# Reference-L.net
KiCad netlist of a schematic drawn in Altium Designer
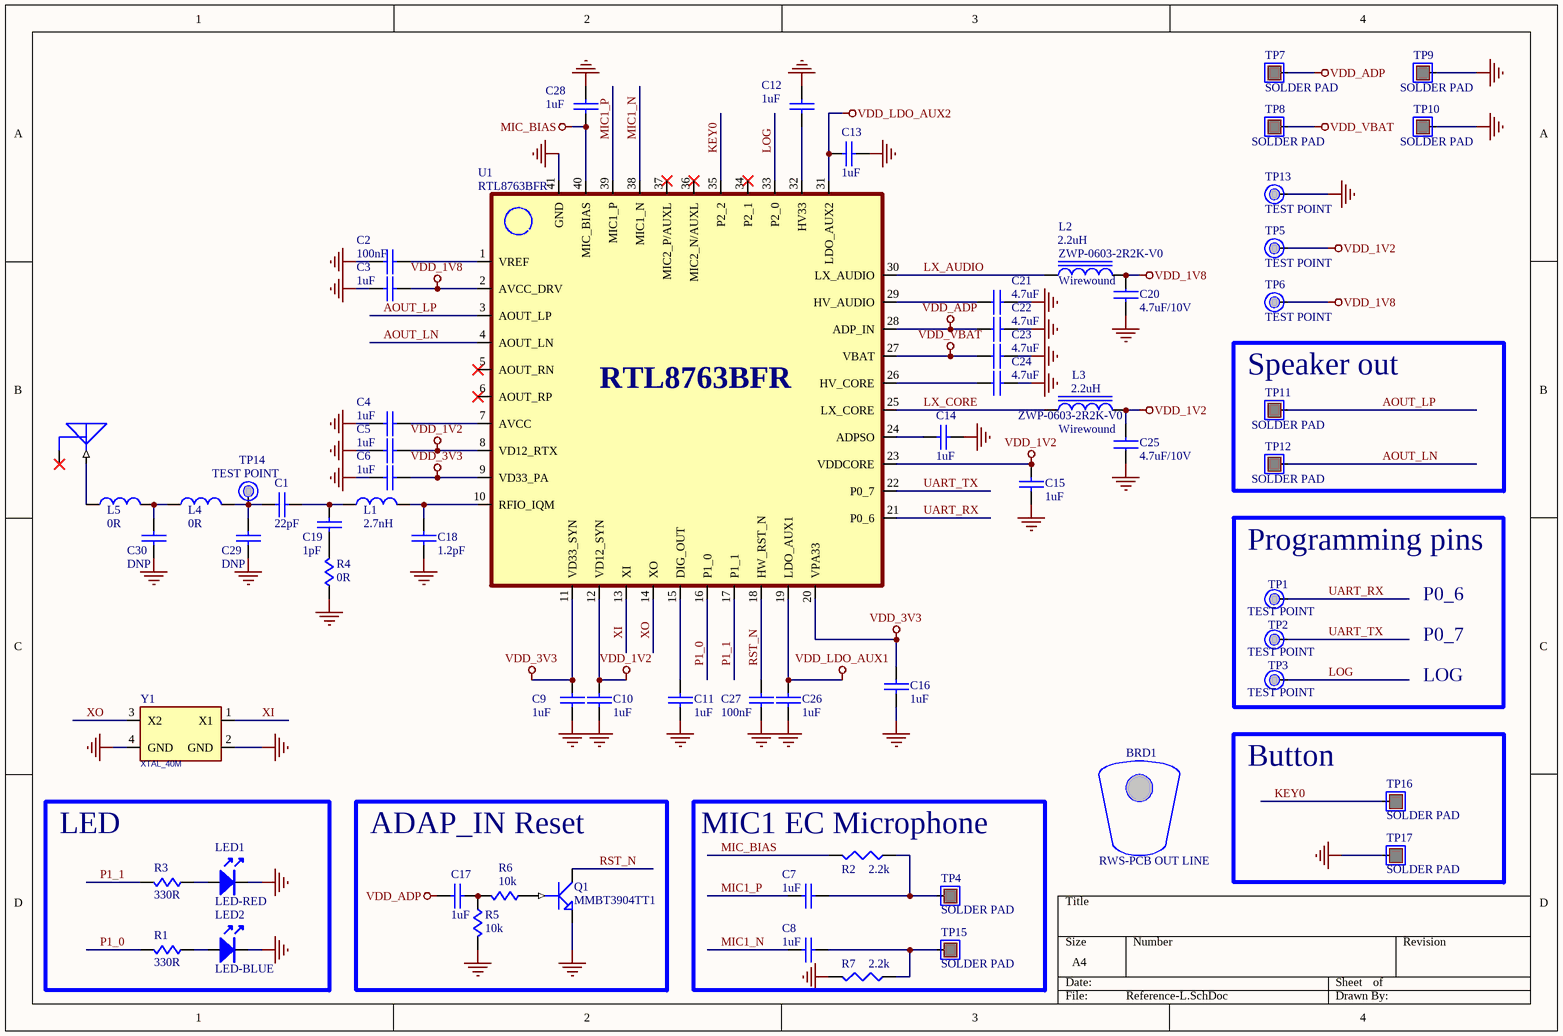
[diagram p0: Reference-L.SchDoc]

(export (version "E")
  (design (tool "Eeschema 10.0.6"))
  (components
    (comp (ref "ANT1")
      (value "ANTENNA-2")
      (footprint "ANT-ACX-AT8010")
      (libsource (lib "*") (part "ANTENNA-2_4"))
    )
    (comp (ref "BRD1")
      (value "RWS-PCB OUT LINE")
      (footprint "BOARD-L")
      (libsource (lib "*") (part "RWS-PCB OUT LINE"))
    )
    (comp (ref "C1")
      (value "22pF")
      (footprint "CAP_0201")
      (description "Capacitor")
      (libsource (lib "*") (part "CAP"))
    )
    (comp (ref "C2")
      (value "100nF")
      (footprint "CAP_0201")
      (description "Capacitor")
      (libsource (lib "*") (part "CAP"))
    )
    (comp (ref "C3")
      (value "1uF")
      (footprint "CAP_0201")
      (description "Capacitor")
      (libsource (lib "*") (part "CAP"))
    )
    (comp (ref "C4")
      (value "1uF")
      (footprint "CAP_0201")
      (description "Capacitor")
      (libsource (lib "*") (part "CAP"))
    )
    (comp (ref "C5")
      (value "1uF")
      (footprint "CAP_0201")
      (description "Capacitor")
      (libsource (lib "*") (part "CAP"))
    )
    (comp (ref "C6")
      (value "1uF")
      (footprint "CAP_0201")
      (description "Capacitor")
      (libsource (lib "*") (part "CAP"))
    )
    (comp (ref "C7")
      (value "1uF")
      (footprint "CAP_0201")
      (description "Capacitor")
      (libsource (lib "*") (part "CAP"))
    )
    (comp (ref "C8")
      (value "1uF")
      (footprint "CAP_0201")
      (description "Capacitor")
      (libsource (lib "*") (part "CAP"))
    )
    (comp (ref "C9")
      (value "1uF")
      (footprint "CAP_0201")
      (description "Capacitor")
      (libsource (lib "*") (part "CAP"))
    )
    (comp (ref "C10")
      (value "1uF")
      (footprint "CAP_0201")
      (description "Capacitor")
      (libsource (lib "*") (part "CAP"))
    )
    (comp (ref "C11")
      (value "1uF")
      (footprint "CAP_0201")
      (description "Capacitor")
      (libsource (lib "*") (part "CAP"))
    )
    (comp (ref "C12")
      (value "1uF")
      (footprint "CAP_0201")
      (description "Capacitor")
      (libsource (lib "*") (part "CAP"))
    )
    (comp (ref "C13")
      (value "1uF")
      (footprint "CAP_0201")
      (description "Capacitor")
      (libsource (lib "*") (part "CAP"))
    )
    (comp (ref "C14")
      (value "1uF")
      (footprint "CAP_0201")
      (description "Capacitor")
      (libsource (lib "*") (part "CAP"))
    )
    (comp (ref "C15")
      (value "1uF")
      (footprint "CAP_0201")
      (description "Capacitor")
      (libsource (lib "*") (part "CAP"))
    )
    (comp (ref "C16")
      (value "1uF")
      (footprint "CAP_0201")
      (description "Capacitor")
      (libsource (lib "*") (part "CAP"))
    )
    (comp (ref "C17")
      (value "1uF")
      (footprint "CAP_0201")
      (description "Capacitor")
      (libsource (lib "*") (part "CAP"))
    )
    (comp (ref "C18")
      (value "1.2pF")
      (footprint "CAP_0201")
      (description "Capacitor")
      (libsource (lib "*") (part "CAP"))
    )
    (comp (ref "C19")
      (value "1pF")
      (footprint "CAP_0201")
      (description "Capacitor")
      (libsource (lib "*") (part "CAP"))
    )
    (comp (ref "C20")
      (value "4.7uF/10V")
      (footprint "CAP_0402")
      (description "CHIP CAP 4.7uF 6.3V K 0603  X5R")
      (fields (field (name "PART NUMBER") "CC0603ZRY5V5BB475") (field (name "TOLERANCE") "+80-20％"))
      (libsource (lib "*") (part "4.7uF"))
    )
    (comp (ref "C21")
      (value "4.7uF")
      (footprint "CAP_0402")
      (description "CHIP CAP 4.7uF 6.3V K 0603  X5R")
      (fields (field (name "PART NUMBER") "CC0603ZRY5V5BB475") (field (name "TOLERANCE") "+80-20％"))
      (libsource (lib "*") (part "4.7uF"))
    )
    (comp (ref "C22")
      (value "4.7uF")
      (footprint "CAP_0402")
      (description "CHIP CAP 4.7uF 6.3V K 0603  X5R")
      (fields (field (name "PART NUMBER") "CC0603ZRY5V5BB475") (field (name "TOLERANCE") "+80-20％"))
      (libsource (lib "*") (part "4.7uF"))
    )
    (comp (ref "C23")
      (value "4.7uF")
      (footprint "CAP_0402")
      (description "CHIP CAP 4.7uF 6.3V K 0603  X5R")
      (fields (field (name "PART NUMBER") "CC0603ZRY5V5BB475") (field (name "TOLERANCE") "+80-20％"))
      (libsource (lib "*") (part "4.7uF"))
    )
    (comp (ref "C24")
      (value "4.7uF")
      (footprint "CAP_0402")
      (description "CHIP CAP 4.7uF 6.3V K 0603  X5R")
      (fields (field (name "PART NUMBER") "CC0603ZRY5V5BB475") (field (name "TOLERANCE") "+80-20％"))
      (libsource (lib "*") (part "4.7uF"))
    )
    (comp (ref "C25")
      (value "4.7uF/10V")
      (footprint "CAP_0402")
      (description "CHIP CAP 4.7uF 6.3V K 0603  X5R")
      (fields (field (name "PART NUMBER") "CC0603ZRY5V5BB475") (field (name "TOLERANCE") "+80-20％"))
      (libsource (lib "*") (part "4.7uF"))
    )
    (comp (ref "C26")
      (value "1uF")
      (footprint "CAP_0201")
      (description "Capacitor")
      (libsource (lib "*") (part "CAP"))
    )
    (comp (ref "C27")
      (value "100nF")
      (footprint "CAP_0201")
      (description "Capacitor")
      (libsource (lib "*") (part "CAP"))
    )
    (comp (ref "C28")
      (value "1uF")
      (footprint "CAP_0201")
      (description "Capacitor")
      (libsource (lib "*") (part "CAP"))
    )
    (comp (ref "C29")
      (value "DNP")
      (footprint "CAP_0201")
      (description "Capacitor")
      (libsource (lib "*") (part "CAP"))
    )
    (comp (ref "C30")
      (value "DNP")
      (footprint "CAP_0201")
      (description "Capacitor")
      (libsource (lib "*") (part "CAP"))
    )
    (comp (ref "L1") (value "2.7nH") (footprint "IND_0201") (libsource (lib "*") (part "INDUCTOR-MINI")))
    (comp (ref "L2") (value "2.2uH") (footprint "IND_0603") (libsource (lib "*") (part "INDUCTOR IRON")))
    (comp (ref "L3") (value "2.2uH") (footprint "IND_0603") (libsource (lib "*") (part "INDUCTOR IRON")))
    (comp (ref "L4") (value "0R") (footprint "IND_0201") (libsource (lib "*") (part "INDUCTOR-MINI")))
    (comp (ref "L5") (value "0R") (footprint "IND_0201") (libsource (lib "*") (part "INDUCTOR-MINI")))
    (comp (ref "LED1") (value "LED-RED") (footprint "LED-0603") (libsource (lib "*") (part "LED")))
    (comp (ref "LED2") (value "LED-BLUE") (footprint "LED-0603") (libsource (lib "*") (part "LED")))
    (comp (ref "Q1") (value "MMBT3904TT1") (footprint "SOT323") (libsource (lib "*") (part "NPN")))
    (comp (ref "R1") (value "330R") (footprint "RES_0201") (libsource (lib "*") (part "RESISTANCE")))
    (comp (ref "R2")
      (value "2.2k")
      (footprint "0201")
      (description "CHIP RES 1.5K 1/16W 0402")
      (fields (field (name "TOLERANCE") "±5％") (field (name "PART NUMBER") "RC0402FR-071K5L"))
      (libsource (lib "*") (part "1.5K"))
    )
    (comp (ref "R3") (value "330R") (footprint "RES_0201") (libsource (lib "*") (part "RESISTANCE")))
    (comp (ref "R4") (value "0R") (footprint "RES_0201") (libsource (lib "*") (part "RESISTANCE")))
    (comp (ref "R5") (value "10k") (footprint "RES_0201") (libsource (lib "*") (part "RESISTANCE")))
    (comp (ref "R6") (value "10k") (footprint "RES_0201") (libsource (lib "*") (part "RESISTANCE")))
    (comp (ref "R7")
      (value "2.2k")
      (footprint "0201")
      (description "CHIP RES 1.5K 1/16W 0402")
      (fields (field (name "TOLERANCE") "±5％") (field (name "PART NUMBER") "RC0402FR-071K5L"))
      (libsource (lib "*") (part "1.5K"))
    )
    (comp (ref "TP1") (value "TEST POINT") (footprint "TP-0.8MM") (libsource (lib "*") (part "TEST POINT")))
    (comp (ref "TP2") (value "TEST POINT") (footprint "TP-0.8MM") (libsource (lib "*") (part "TEST POINT")))
    (comp (ref "TP3") (value "TEST POINT") (footprint "TP-0.8MM") (libsource (lib "*") (part "TEST POINT")))
    (comp (ref "TP4")
      (value "SOLDER PAD")
      (footprint "TP-SOLDER")
      (libsource (lib "") (part "TEST POINT-SQ_1"))
    )
    (comp (ref "TP5") (value "TEST POINT") (footprint "TP-0.8MM") (libsource (lib "*") (part "TEST POINT")))
    (comp (ref "TP6") (value "TEST POINT") (footprint "TP-0.8MM") (libsource (lib "*") (part "TEST POINT")))
    (comp (ref "TP7")
      (value "SOLDER PAD")
      (footprint "TP-SOLDER-SQ")
      (libsource (lib "*") (part "TEST POINT-SQ"))
    )
    (comp (ref "TP8")
      (value "SOLDER PAD")
      (footprint "TP-SOLDER-SQ")
      (libsource (lib "*") (part "TEST POINT-SQ"))
    )
    (comp (ref "TP9")
      (value "SOLDER PAD")
      (footprint "TP-SOLDER")
      (libsource (lib "*") (part "TEST POINT-SQ"))
    )
    (comp (ref "TP10")
      (value "SOLDER PAD")
      (footprint "TP-SOLDER")
      (libsource (lib "*") (part "TEST POINT-SQ"))
    )
    (comp (ref "TP11")
      (value "SOLDER PAD")
      (footprint "TP-SOLDER")
      (libsource (lib "*") (part "TEST POINT-SQ"))
    )
    (comp (ref "TP12")
      (value "SOLDER PAD")
      (footprint "TP-SOLDER")
      (libsource (lib "*") (part "TEST POINT-SQ"))
    )
    (comp (ref "TP13") (value "TEST POINT") (footprint "TP-0.8MM") (libsource (lib "*") (part "TEST POINT")))
    (comp (ref "TP14") (value "TEST POINT") (footprint "TP-0.8MM") (libsource (lib "*") (part "TEST POINT")))
    (comp (ref "TP15")
      (value "SOLDER PAD")
      (footprint "TP-SOLDER")
      (libsource (lib "") (part "TEST POINT-SQ_1"))
    )
    (comp (ref "TP16")
      (value "SOLDER PAD")
      (footprint "TP-SOLDER-SQ")
      (libsource (lib "") (part "TEST POINT-SQ_1"))
    )
    (comp (ref "TP17")
      (value "SOLDER PAD")
      (footprint "TP-SOLDER-SQ")
      (libsource (lib "") (part "TEST POINT-SQ_1"))
    )
    (comp (ref "U1")
      (value "RTL8763BFR")
      (footprint "QFN40-0.4-5X5")
      (description "RTL8763")
      (libsource (lib "*") (part "RTL8763"))
    )
    (comp (ref "Y1")
      (value "XTAL_40M")
      (footprint "CRY_2.5X2.0")
      (description "S2520A-040000-T12-BBK-1AHA(YOKE)")
      (fields (field (name "PART NUMBER") "40M xtal 2.5x2.0"))
      (libsource (lib "*") (part "XTAL"))
    )
  )
  (nets
    (net (code "1") (name "/AOUT_LN") (class "Default")
      (node (ref "TP12") (pin "1") (pinfunction "1_1") (pintype "passive"))
      (node (ref "U1") (pin "4") (pinfunction "AOUT_LN_4") (pintype "passive"))
    )
    (net (code "2") (name "/AOUT_LP") (class "Default")
      (node (ref "TP11") (pin "1") (pinfunction "1_1") (pintype "passive"))
      (node (ref "U1") (pin "3") (pinfunction "AOUT_LP_3") (pintype "passive"))
    )
    (net (code "3") (name "/KEY0") (class "Default")
      (node (ref "TP16") (pin "1") (pinfunction "1_1") (pintype "passive"))
      (node (ref "U1") (pin "35") (pinfunction "P2_2_35") (pintype "passive"))
    )
    (net (code "4") (name "/LOG") (class "Default")
      (node (ref "TP3") (pin "1") (pinfunction "1_1") (pintype "passive"))
      (node (ref "U1") (pin "33") (pinfunction "P2_0_33") (pintype "passive"))
    )
    (net (code "5") (name "/LX_AUDIO") (class "Default")
      (node (ref "L2") (pin "1") (pinfunction "1_1") (pintype "passive"))
      (node (ref "U1") (pin "30") (pinfunction "LX_AUDIO_30") (pintype "passive"))
    )
    (net (code "6") (name "/LX_CORE") (class "Default")
      (node (ref "L3") (pin "1") (pinfunction "1_1") (pintype "passive"))
      (node (ref "U1") (pin "25") (pinfunction "LX_CORE_25") (pintype "passive"))
    )
    (net (code "7") (name "/MIC1_N") (class "Default")
      (node (ref "C8") (pin "1") (pinfunction "1_1") (pintype "passive"))
      (node (ref "U1") (pin "38") (pinfunction "MIC1_N_38") (pintype "passive"))
    )
    (net (code "8") (name "/MIC1_P") (class "Default")
      (node (ref "C7") (pin "1") (pinfunction "1_1") (pintype "passive"))
      (node (ref "U1") (pin "39") (pinfunction "MIC1_P_39") (pintype "passive"))
    )
    (net (code "9") (name "/P1_0") (class "Default")
      (node (ref "R1") (pin "2") (pinfunction "2_2") (pintype "passive"))
      (node (ref "U1") (pin "16") (pinfunction "P1_0_16") (pintype "passive"))
    )
    (net (code "10") (name "/P1_1") (class "Default")
      (node (ref "R3") (pin "2") (pinfunction "2_2") (pintype "passive"))
      (node (ref "U1") (pin "17") (pinfunction "P1_1_17") (pintype "passive"))
    )
    (net (code "11") (name "/RST_N") (class "Default")
      (node (ref "C27") (pin "1") (pinfunction "1_1") (pintype "passive"))
      (node (ref "Q1") (pin "3") (pinfunction "C_3") (pintype "passive"))
      (node (ref "U1") (pin "18") (pinfunction "HW_RST_N_18") (pintype "passive"))
    )
    (net (code "12") (name "/UART_RX") (class "Default")
      (node (ref "TP1") (pin "1") (pinfunction "1_1") (pintype "passive"))
      (node (ref "U1") (pin "21") (pinfunction "P0_6_21") (pintype "passive"))
    )
    (net (code "13") (name "/UART_TX") (class "Default")
      (node (ref "TP2") (pin "1") (pinfunction "1_1") (pintype "passive"))
      (node (ref "U1") (pin "22") (pinfunction "P0_7_22") (pintype "passive"))
    )
    (net (code "14") (name "/XI") (class "Default")
      (node (ref "U1") (pin "13") (pinfunction "XI_13") (pintype "passive"))
      (node (ref "Y1") (pin "1") (pinfunction "X1_1") (pintype "passive"))
    )
    (net (code "15") (name "/XO") (class "Default")
      (node (ref "U1") (pin "14") (pinfunction "XO_14") (pintype "passive"))
      (node (ref "Y1") (pin "3") (pinfunction "X2_3") (pintype "passive"))
    )
    (net (code "16") (name "GND") (class "Default")
      (node (ref "C10") (pin "2") (pinfunction "2_2") (pintype "passive"))
      (node (ref "C11") (pin "2") (pinfunction "2_2") (pintype "passive"))
      (node (ref "C12") (pin "2") (pinfunction "2_2") (pintype "passive"))
      (node (ref "C13") (pin "2") (pinfunction "2_2") (pintype "passive"))
      (node (ref "C14") (pin "2") (pinfunction "2_2") (pintype "passive"))
      (node (ref "C15") (pin "2") (pinfunction "2_2") (pintype "passive"))
      (node (ref "C16") (pin "2") (pinfunction "2_2") (pintype "passive"))
      (node (ref "C18") (pin "2") (pinfunction "2_2") (pintype "passive"))
      (node (ref "C2") (pin "2") (pinfunction "2_2") (pintype "passive"))
      (node (ref "C20") (pin "2") (pinfunction "2_2") (pintype "passive"))
      (node (ref "C21") (pin "2") (pinfunction "2_2") (pintype "passive"))
      (node (ref "C22") (pin "2") (pinfunction "2_2") (pintype "passive"))
      (node (ref "C23") (pin "2") (pinfunction "2_2") (pintype "passive"))
      (node (ref "C24") (pin "2") (pinfunction "2_2") (pintype "passive"))
      (node (ref "C25") (pin "1") (pinfunction "1_1") (pintype "passive"))
      (node (ref "C26") (pin "2") (pinfunction "2_2") (pintype "passive"))
      (node (ref "C27") (pin "2") (pinfunction "2_2") (pintype "passive"))
      (node (ref "C28") (pin "2") (pinfunction "2_2") (pintype "passive"))
      (node (ref "C29") (pin "2") (pinfunction "2_2") (pintype "passive"))
      (node (ref "C3") (pin "2") (pinfunction "2_2") (pintype "passive"))
      (node (ref "C30") (pin "2") (pinfunction "2_2") (pintype "passive"))
      (node (ref "C4") (pin "2") (pinfunction "2_2") (pintype "passive"))
      (node (ref "C5") (pin "2") (pinfunction "2_2") (pintype "passive"))
      (node (ref "C6") (pin "2") (pinfunction "2_2") (pintype "passive"))
      (node (ref "C9") (pin "2") (pinfunction "2_2") (pintype "passive"))
      (node (ref "LED1") (pin "2") (pinfunction "K_2") (pintype "passive"))
      (node (ref "LED2") (pin "2") (pinfunction "K_2") (pintype "passive"))
      (node (ref "Q1") (pin "2") (pinfunction "E_2") (pintype "passive"))
      (node (ref "R4") (pin "1") (pinfunction "1_1") (pintype "passive"))
      (node (ref "R5") (pin "2") (pinfunction "2_2") (pintype "passive"))
      (node (ref "R7") (pin "2") (pinfunction "2_2") (pintype "passive"))
      (node (ref "TP10") (pin "1") (pinfunction "1_1") (pintype "passive"))
      (node (ref "TP13") (pin "1") (pinfunction "1_1") (pintype "passive"))
      (node (ref "TP17") (pin "1") (pinfunction "1_1") (pintype "passive"))
      (node (ref "TP9") (pin "1") (pinfunction "1_1") (pintype "passive"))
      (node (ref "U1") (pin "41") (pinfunction "GND_41") (pintype "passive"))
      (node (ref "Y1") (pin "2") (pinfunction "GND_2") (pintype "passive"))
      (node (ref "Y1") (pin "4") (pinfunction "GND_4") (pintype "passive"))
    )
    (net (code "17") (name "MIC_BIAS") (class "Default")
      (node (ref "C28") (pin "1") (pinfunction "1_1") (pintype "passive"))
      (node (ref "R2") (pin "2") (pinfunction "2_2") (pintype "passive"))
      (node (ref "U1") (pin "40") (pinfunction "MIC_BIAS_40") (pintype "passive"))
    )
    (net (code "18") (name "Net-(ANT1-FEED)") (class "Default")
      (node (ref "ANT1") (pin "1") (pinfunction "FEED_1") (pintype "input"))
      (node (ref "L5") (pin "1") (pinfunction "1_1") (pintype "passive"))
    )
    (net (code "19") (name "Net-(C1-Pad1)") (class "Default")
      (node (ref "C1") (pin "1") (pinfunction "1_1") (pintype "passive"))
      (node (ref "C29") (pin "1") (pinfunction "1_1") (pintype "passive"))
      (node (ref "L4") (pin "2") (pinfunction "2_2") (pintype "passive"))
      (node (ref "TP14") (pin "1") (pinfunction "1_1") (pintype "passive"))
    )
    (net (code "20") (name "Net-(C1-Pad2)") (class "Default")
      (node (ref "C1") (pin "2") (pinfunction "2_2") (pintype "passive"))
      (node (ref "C19") (pin "1") (pinfunction "1_1") (pintype "passive"))
      (node (ref "L1") (pin "1") (pinfunction "1_1") (pintype "passive"))
    )
    (net (code "21") (name "Net-(C7-Pad2)") (class "Default")
      (node (ref "C7") (pin "2") (pinfunction "2_2") (pintype "passive"))
      (node (ref "R2") (pin "1") (pinfunction "1_1") (pintype "passive"))
      (node (ref "TP4") (pin "1") (pinfunction "1_1") (pintype "passive"))
    )
    (net (code "22") (name "Net-(C8-Pad2)") (class "Default")
      (node (ref "C8") (pin "2") (pinfunction "2_2") (pintype "passive"))
      (node (ref "R7") (pin "1") (pinfunction "1_1") (pintype "passive"))
      (node (ref "TP15") (pin "1") (pinfunction "1_1") (pintype "passive"))
    )
    (net (code "23") (name "Net-(C17-Pad1)") (class "Default")
      (node (ref "C17") (pin "1") (pinfunction "1_1") (pintype "passive"))
      (node (ref "R5") (pin "1") (pinfunction "1_1") (pintype "passive"))
      (node (ref "R6") (pin "2") (pinfunction "2_2") (pintype "passive"))
    )
    (net (code "24") (name "Net-(C19-Pad2)") (class "Default")
      (node (ref "C19") (pin "2") (pinfunction "2_2") (pintype "passive"))
      (node (ref "R4") (pin "2") (pinfunction "2_2") (pintype "passive"))
    )
    (net (code "25") (name "Net-(C30-Pad1)") (class "Default")
      (node (ref "C30") (pin "1") (pinfunction "1_1") (pintype "passive"))
      (node (ref "L4") (pin "1") (pinfunction "1_1") (pintype "passive"))
      (node (ref "L5") (pin "2") (pinfunction "2_2") (pintype "passive"))
    )
    (net (code "26") (name "Net-(LED1-A)") (class "Default")
      (node (ref "LED1") (pin "1") (pinfunction "A_1") (pintype "passive"))
      (node (ref "R3") (pin "1") (pinfunction "1_1") (pintype "passive"))
    )
    (net (code "27") (name "Net-(LED2-A)") (class "Default")
      (node (ref "LED2") (pin "1") (pinfunction "A_1") (pintype "passive"))
      (node (ref "R1") (pin "1") (pinfunction "1_1") (pintype "passive"))
    )
    (net (code "28") (name "Net-(Q1-B)") (class "Default")
      (node (ref "Q1") (pin "1") (pinfunction "B_1") (pintype "input"))
      (node (ref "R6") (pin "1") (pinfunction "1_1") (pintype "passive"))
    )
    (net (code "29") (name "Net-(U1-ADPSO)") (class "Default")
      (node (ref "C14") (pin "1") (pinfunction "1_1") (pintype "passive"))
      (node (ref "U1") (pin "24") (pinfunction "ADPSO_24") (pintype "passive"))
    )
    (net (code "30") (name "Net-(U1-AVCC)") (class "Default")
      (node (ref "C4") (pin "1") (pinfunction "1_1") (pintype "passive"))
      (node (ref "U1") (pin "7") (pinfunction "AVCC_7") (pintype "passive"))
    )
    (net (code "31") (name "Net-(U1-DIG_OUT)") (class "Default")
      (node (ref "C11") (pin "1") (pinfunction "1_1") (pintype "passive"))
      (node (ref "U1") (pin "15") (pinfunction "DIG_OUT_15") (pintype "passive"))
    )
    (net (code "32") (name "Net-(U1-HV33)") (class "Default")
      (node (ref "C12") (pin "1") (pinfunction "1_1") (pintype "passive"))
      (node (ref "U1") (pin "32") (pinfunction "HV33_32") (pintype "passive"))
    )
    (net (code "33") (name "Net-(U1-HV_AUDIO)") (class "Default")
      (node (ref "C21") (pin "1") (pinfunction "1_1") (pintype "passive"))
      (node (ref "U1") (pin "29") (pinfunction "HV_AUDIO_29") (pintype "passive"))
    )
    (net (code "34") (name "Net-(U1-HV_CORE)") (class "Default")
      (node (ref "C24") (pin "1") (pinfunction "1_1") (pintype "passive"))
      (node (ref "U1") (pin "26") (pinfunction "HV_CORE_26") (pintype "passive"))
    )
    (net (code "35") (name "Net-(U1-RFIO_IQM)") (class "Default")
      (node (ref "C18") (pin "1") (pinfunction "1_1") (pintype "passive"))
      (node (ref "L1") (pin "2") (pinfunction "2_2") (pintype "passive"))
      (node (ref "U1") (pin "10") (pinfunction "RFIO_IQM_10") (pintype "passive"))
    )
    (net (code "36") (name "Net-(U1-VREF)") (class "Default")
      (node (ref "C2") (pin "1") (pinfunction "1_1") (pintype "passive"))
      (node (ref "U1") (pin "1") (pinfunction "VREF_1") (pintype "passive"))
    )
    (net (code "37") (name "VDD_1V2") (class "Default")
      (node (ref "C10") (pin "1") (pinfunction "1_1") (pintype "passive"))
      (node (ref "C15") (pin "1") (pinfunction "1_1") (pintype "passive"))
      (node (ref "C25") (pin "2") (pinfunction "2_2") (pintype "passive"))
      (node (ref "C5") (pin "1") (pinfunction "1_1") (pintype "passive"))
      (node (ref "L3") (pin "2") (pinfunction "2_2") (pintype "passive"))
      (node (ref "TP5") (pin "1") (pinfunction "1_1") (pintype "passive"))
      (node (ref "U1") (pin "12") (pinfunction "VD12_SYN_12") (pintype "passive"))
      (node (ref "U1") (pin "23") (pinfunction "VDDCORE_23") (pintype "passive"))
      (node (ref "U1") (pin "8") (pinfunction "VD12_RTX_8") (pintype "passive"))
    )
    (net (code "38") (name "VDD_1V8") (class "Default")
      (node (ref "C20") (pin "1") (pinfunction "1_1") (pintype "passive"))
      (node (ref "C3") (pin "1") (pinfunction "1_1") (pintype "passive"))
      (node (ref "L2") (pin "2") (pinfunction "2_2") (pintype "passive"))
      (node (ref "TP6") (pin "1") (pinfunction "1_1") (pintype "passive"))
      (node (ref "U1") (pin "2") (pinfunction "AVCC_DRV_2") (pintype "passive"))
    )
    (net (code "39") (name "VDD_3V3") (class "Default")
      (node (ref "C16") (pin "1") (pinfunction "1_1") (pintype "passive"))
      (node (ref "C6") (pin "1") (pinfunction "1_1") (pintype "passive"))
      (node (ref "C9") (pin "1") (pinfunction "1_1") (pintype "passive"))
      (node (ref "U1") (pin "11") (pinfunction "VD33_SYN_11") (pintype "passive"))
      (node (ref "U1") (pin "20") (pinfunction "VPA33_20") (pintype "passive"))
      (node (ref "U1") (pin "9") (pinfunction "VD33_PA_9") (pintype "passive"))
    )
    (net (code "40") (name "VDD_ADP") (class "Default")
      (node (ref "C17") (pin "2") (pinfunction "2_2") (pintype "passive"))
      (node (ref "C22") (pin "1") (pinfunction "1_1") (pintype "passive"))
      (node (ref "TP7") (pin "1") (pinfunction "1_1") (pintype "passive"))
      (node (ref "U1") (pin "28") (pinfunction "ADP_IN_28") (pintype "passive"))
    )
    (net (code "41") (name "VDD_LDO_AUX1") (class "Default")
      (node (ref "C26") (pin "1") (pinfunction "1_1") (pintype "passive"))
      (node (ref "U1") (pin "19") (pinfunction "LDO_AUX1_19") (pintype "passive"))
    )
    (net (code "42") (name "VDD_LDO_AUX2") (class "Default")
      (node (ref "C13") (pin "1") (pinfunction "1_1") (pintype "passive"))
      (node (ref "U1") (pin "31") (pinfunction "LDO_AUX2_31") (pintype "passive"))
    )
    (net (code "43") (name "VDD_VBAT") (class "Default")
      (node (ref "C23") (pin "1") (pinfunction "1_1") (pintype "passive"))
      (node (ref "TP8") (pin "1") (pinfunction "1_1") (pintype "passive"))
      (node (ref "U1") (pin "27") (pinfunction "VBAT_27") (pintype "passive"))
    )
    (net (code "44") (name "unconnected-(ANT1-GND-Pad2)") (class "Default")
      (node (ref "ANT1") (pin "2") (pinfunction "GND_2") (pintype "passive+no_connect"))
    )
    (net (code "45") (name "unconnected-(U1-AOUT_RN-Pad5)") (class "Default")
      (node (ref "U1") (pin "5") (pinfunction "AOUT_RN_5") (pintype "passive+no_connect"))
    )
    (net (code "46") (name "unconnected-(U1-AOUT_RP-Pad6)") (class "Default")
      (node (ref "U1") (pin "6") (pinfunction "AOUT_RP_6") (pintype "passive+no_connect"))
    )
    (net (code "47") (name "unconnected-(U1-MIC2_N{slash}AUXL-Pad36)") (class "Default")
      (node (ref "U1") (pin "36") (pinfunction "MIC2_N/AUXL_36") (pintype "passive+no_connect"))
    )
    (net (code "48") (name "unconnected-(U1-MIC2_P{slash}AUXL-Pad37)") (class "Default")
      (node (ref "U1") (pin "37") (pinfunction "MIC2_P/AUXL_37") (pintype "passive+no_connect"))
    )
    (net (code "49") (name "unconnected-(U1-P2_1-Pad34)") (class "Default")
      (node (ref "U1") (pin "34") (pinfunction "P2_1_34") (pintype "passive+no_connect"))
    )
  )
)
